# Relay_Channel.net
KiCad netlist of a schematic drawn in Altium Designer
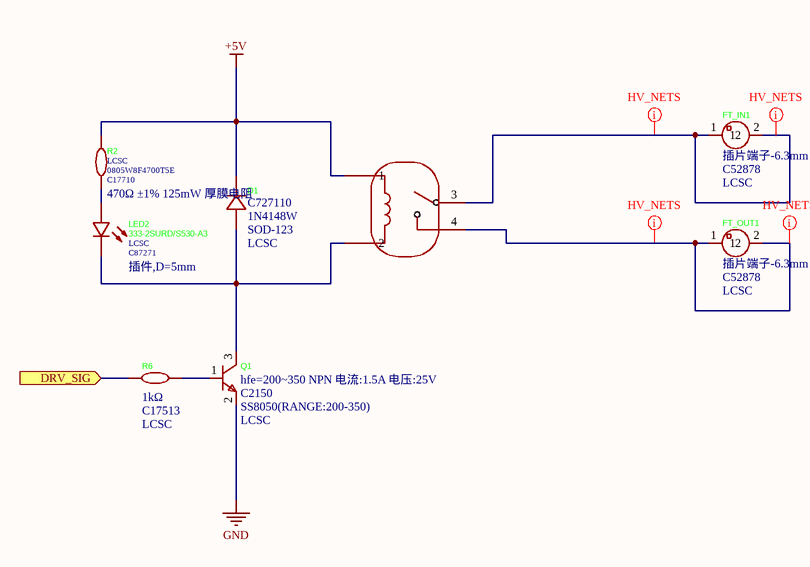
[diagram p0: Relay_Channel.SchDoc]

(export (version "E")
  (design (tool "Eeschema 10.0.6"))
  (components
    (comp (ref "D1")
      (value "1N4148W")
      (footprint "SOD-123_L3.1-W1.7-LS3.7-RD")
      (fields
        (field (name "MANUFACTURER") "TWGMC(台湾迪嘉)")
        (field (name "SUPPLIER PART") "C727110")
        (field (name "MANUFACTURER PART") "1N4148W")
        (field (name "SUPPLIER FOOTPRINT") "SOD-123")
        (field (name "SUPPLIER") "LCSC")
      )
      (libsource (lib "1N4148W_C727110") (part "1N4148W_C727110"))
    )
    (comp (ref "FT_IN1")
      (value "EST026")
      (footprint "CONN-TH_L6.3-W0.8-EST026")
      (fields
        (field (name "MANUFACTURER") "xcfuse(旭程)")
        (field (name "LCSC PART NAME") "插片端子-6.3mm")
        (field (name "SUPPLIER PART") "C52878")
        (field (name "SUPPLIER") "LCSC")
      )
      (libsource (lib "EST0261") (part "EST026"))
    )
    (comp (ref "FT_OUT1")
      (value "EST026")
      (footprint "CONN-TH_L6.3-W0.8-EST026")
      (fields
        (field (name "MANUFACTURER") "xcfuse(旭程)")
        (field (name "LCSC PART NAME") "插片端子-6.3mm")
        (field (name "SUPPLIER PART") "C52878")
        (field (name "SUPPLIER") "LCSC")
      )
      (libsource (lib "EST0261") (part "EST026"))
    )
    (comp (ref "K1")
      (value "HF105F-1/005D-1HST")
      (footprint "HF105F-1_005D-1HST1_Update:HF105F-1_005D-1HST1_Update")
      (fields (field (name "MANUFACTURER") "HF(宏发)"))
      (libsource (lib "HF105F-1_005D-1HST1_Updated") (part "HF105F-1/005D-1HST"))
    )
    (comp (ref "LED2")
      (value "333-2SURD/S530-A3")
      (footprint "LED-TH_BD5.9-P2.54-RD_RED:LED-TH_BD5.9-P2.54-RD_RED")
      (fields
        (field (name "MANUFACTURER") "EVERLIGHT(亿光)")
        (field (name "SUPPLIER") "LCSC")
        (field (name "SUPPLIER PART") "C87271")
        (field (name "SUPPLIER FOOTPRINT") "插件,D=5mm")
      )
      (libsource (lib "333-2SURD_S530-A31_333-2SURD_S530-A3") (part "333-2SURD/S530-A3"))
    )
    (comp (ref "Q1")
      (value "SS8050(RANGE:200-350)")
      (footprint "SOT-23-3_L2.9-W1.3-P1.90-LS2.4-BR")
      (fields
        (field (name "MANUFACTURER") "CJ(江苏长电/长晶)")
        (field (name "LCSC PART NAME") "hfe=200~350 NPN 电流:1.5A 电压:25V")
        (field (name "SUPPLIER PART") "C2150")
        (field (name "MANUFACTURER PART") "SS8050(RANGE:200-350)")
        (field (name "SUPPLIER") "LCSC")
      )
      (libsource (lib "SS8050_C21501") (part "SS8050(RANGE{colon}200-350)_C2150"))
    )
    (comp (ref "R2")
      (value "470Ω")
      (footprint "R0805")
      (fields
        (field (name "MANUFACTURER") "UNI-ROYAL(厚声)")
        (field (name "TOLERANCE") "±1%")
        (field (name "SUPPLIER") "LCSC")
        (field (name "MANUFACTURER PART") "0805W8F4700T5E")
        (field (name "SUPPLIER PART") "C17710")
        (field (name "LCSC PART NAME") "470Ω ±1% 125mW 厚膜电阻")
      )
      (libsource (lib "RES_470_0805W") (part "0805W8F4700T5E"))
    )
    (comp (ref "R6")
      (value "1kΩ")
      (footprint "R0805")
      (fields
        (field (name "MANUFACTURER") "UNI-ROYAL(厚声)")
        (field (name "TOLERANCE") "±1%")
        (field (name "SUPPLIER PART") "C17513")
        (field (name "MANUFACTURER PART") "0805W8F1001T5E")
        (field (name "SUPPLIER") "LCSC")
      )
      (libsource (lib "1k_0805W8F1001T5E1") (part "0805W8F1001T5E"))
    )
  )
  (nets
    (net (code "1") (name "+5V") (class "Default")
      (node (ref "D1") (pin "1") (pinfunction "K_1") (pintype "passive"))
      (node (ref "K1") (pin "1") (pinfunction "1_1") (pintype "passive"))
      (node (ref "R2") (pin "2") (pinfunction "2_2") (pintype "passive"))
    )
    (net (code "2") (name "/DRV_SIG") (class "Default")
      (node (ref "R6") (pin "1") (pinfunction "1_1") (pintype "passive"))
    )
    (net (code "3") (name "GND") (class "Default")
      (node (ref "Q1") (pin "2") (pinfunction "E_2") (pintype "passive"))
    )
    (net (code "4") (name "Net-(D1-A)") (class "Default")
      (node (ref "D1") (pin "2") (pinfunction "A_2") (pintype "passive"))
      (node (ref "K1") (pin "2") (pinfunction "2_2") (pintype "passive"))
      (node (ref "LED2") (pin "1") (pinfunction "C_1") (pintype "passive"))
      (node (ref "Q1") (pin "3") (pinfunction "C_3") (pintype "passive"))
    )
    (net (code "5") (name "Net-(FT_IN1-Pad1)") (class "Default")
      (node (ref "FT_IN1") (pin "1") (pinfunction "1_1") (pintype "passive"))
      (node (ref "FT_IN1") (pin "2") (pinfunction "2_2") (pintype "passive"))
      (node (ref "K1") (pin "3") (pinfunction "3_3") (pintype "passive"))
    )
    (net (code "6") (name "Net-(FT_OUT1-Pad1)") (class "Default")
      (node (ref "FT_OUT1") (pin "1") (pinfunction "1_1") (pintype "passive"))
      (node (ref "FT_OUT1") (pin "2") (pinfunction "2_2") (pintype "passive"))
      (node (ref "K1") (pin "4") (pinfunction "4_4") (pintype "passive"))
    )
    (net (code "7") (name "Net-(LED2-A)") (class "Default")
      (node (ref "LED2") (pin "2") (pinfunction "A_2") (pintype "passive"))
      (node (ref "R2") (pin "1") (pinfunction "1_1") (pintype "passive"))
    )
    (net (code "8") (name "Net-(Q1-B)") (class "Default")
      (node (ref "Q1") (pin "1") (pinfunction "B_1") (pintype "passive"))
      (node (ref "R6") (pin "2") (pinfunction "2_2") (pintype "passive"))
    )
  )
)
